# Servo-Power.net
KiCad netlist of a schematic drawn in Altium Designer
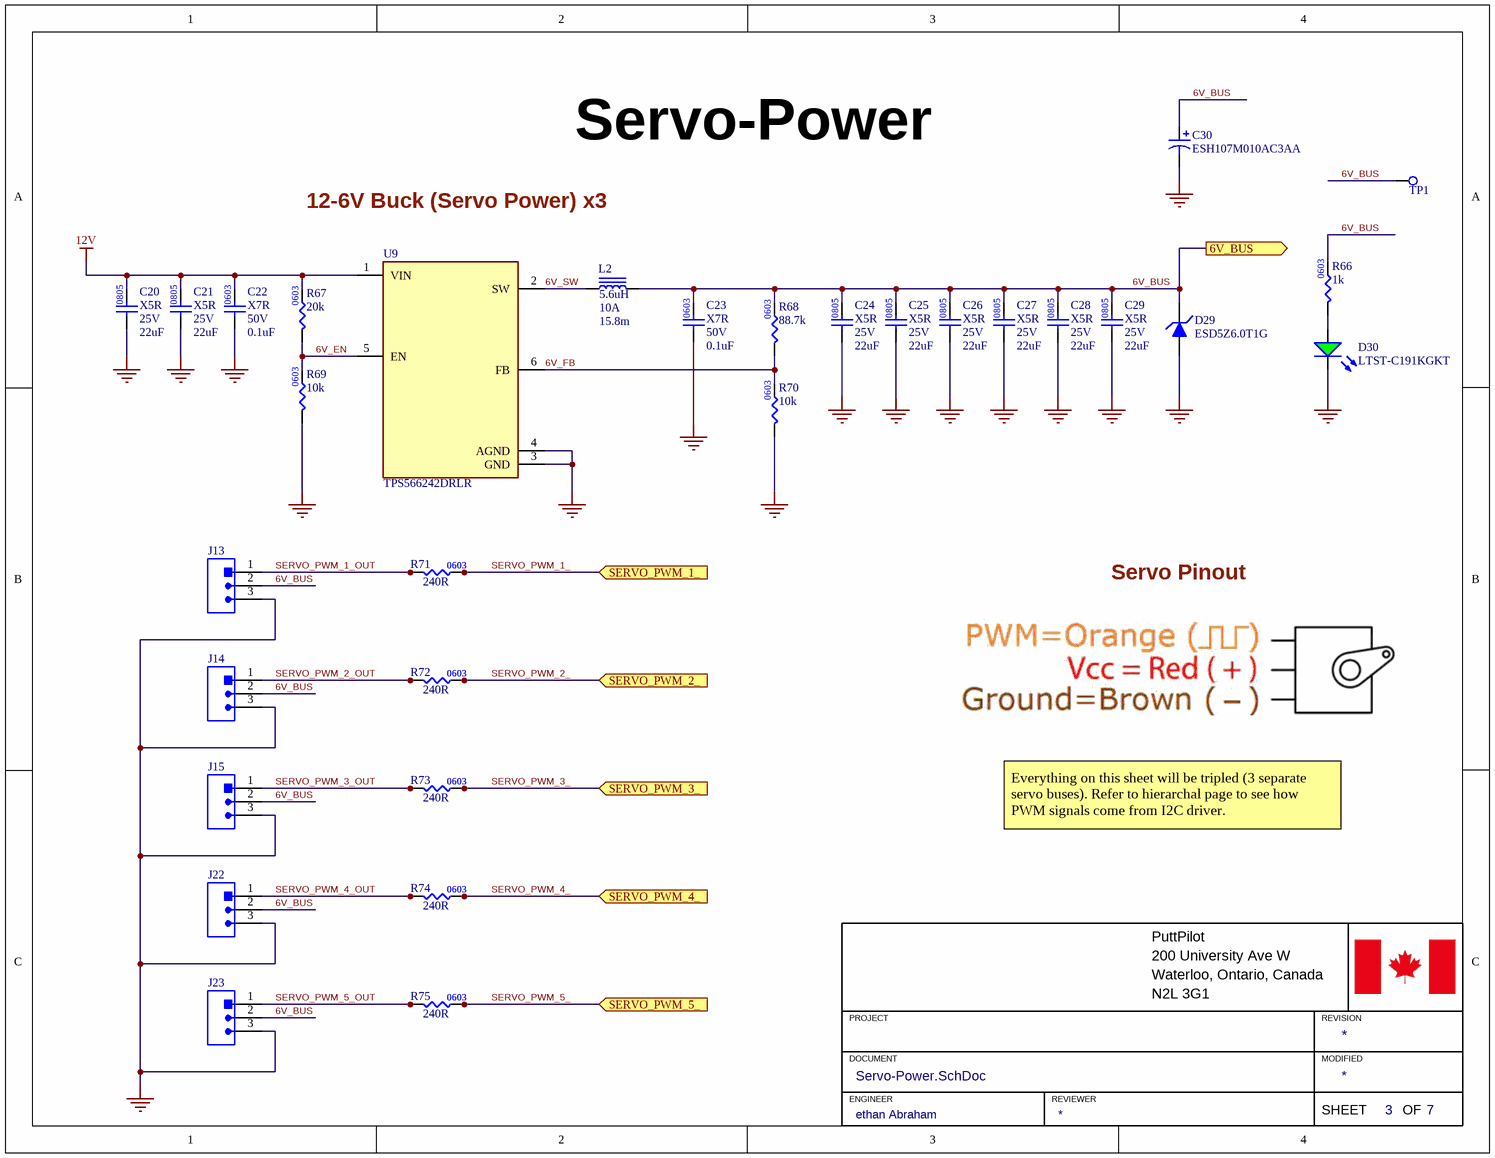
[diagram p0: Servo-Power.SchDoc]

(export (version "E")
  (design (tool "Eeschema 10.0.6"))
  (components
    (comp (ref "C20")
      (value "GRM21BR61E226ME44K")
      (footprint ".CAP_0805")
      (description "CAP CER 22uF 25V X5R 0805")
      (fields
        (field (name "MANUFACTURER") "Murata")
        (field (name "TEMPERATURE CHARACTERISTICS CODE") "X5R")
        (field (name "RATED DC VOLTAGE (URDC)") "25V")
        (field (name "CAPACITANCE") "22uF")
      )
      (libsource (lib "PuttPilot") (part "GRM21BR61E226ME44K"))
    )
    (comp (ref "C21")
      (value "GRM21BR61E226ME44K")
      (footprint ".CAP_0805")
      (description "CAP CER 22uF 25V X5R 0805")
      (fields
        (field (name "MANUFACTURER") "Murata")
        (field (name "TEMPERATURE CHARACTERISTICS CODE") "X5R")
        (field (name "RATED DC VOLTAGE (URDC)") "25V")
        (field (name "CAPACITANCE") "22uF")
      )
      (libsource (lib "PuttPilot") (part "GRM21BR61E226ME44K"))
    )
    (comp (ref "C22")
      (value "GCJ188R71H104KA12D")
      (footprint ".CAP_0603")
      (description "CAP CER 0.1uF 50V X7R 0603")
      (fields
        (field (name "MANUFACTURER") "Murata")
        (field (name "TEMPERATURE CHARACTERISTICS CODE") "X7R")
        (field (name "RATED DC VOLTAGE (URDC)") "50V")
        (field (name "CAPACITANCE") "0.1uF")
      )
      (libsource (lib "PuttPilot") (part "GCJ188R71H104KA12D"))
    )
    (comp (ref "C23")
      (value "GCJ188R71H104KA12D")
      (footprint ".CAP_0603")
      (description "CAP CER 0.1uF 50V X7R 0603")
      (fields
        (field (name "MANUFACTURER") "Murata")
        (field (name "TEMPERATURE CHARACTERISTICS CODE") "X7R")
        (field (name "RATED DC VOLTAGE (URDC)") "50V")
        (field (name "CAPACITANCE") "0.1uF")
      )
      (libsource (lib "PuttPilot") (part "GCJ188R71H104KA12D"))
    )
    (comp (ref "C24")
      (value "GRM21BR61E226ME44K")
      (footprint ".CAP_0805")
      (description "CAP CER 22uF 25V X5R 0805")
      (fields
        (field (name "MANUFACTURER") "Murata")
        (field (name "TEMPERATURE CHARACTERISTICS CODE") "X5R")
        (field (name "RATED DC VOLTAGE (URDC)") "25V")
        (field (name "CAPACITANCE") "22uF")
      )
      (libsource (lib "PuttPilot") (part "GRM21BR61E226ME44K"))
    )
    (comp (ref "C25")
      (value "GRM21BR61E226ME44K")
      (footprint ".CAP_0805")
      (description "CAP CER 22uF 25V X5R 0805")
      (fields
        (field (name "MANUFACTURER") "Murata")
        (field (name "TEMPERATURE CHARACTERISTICS CODE") "X5R")
        (field (name "RATED DC VOLTAGE (URDC)") "25V")
        (field (name "CAPACITANCE") "22uF")
      )
      (libsource (lib "PuttPilot") (part "GRM21BR61E226ME44K"))
    )
    (comp (ref "C26")
      (value "GRM21BR61E226ME44K")
      (footprint ".CAP_0805")
      (description "CAP CER 22uF 25V X5R 0805")
      (fields
        (field (name "MANUFACTURER") "Murata")
        (field (name "TEMPERATURE CHARACTERISTICS CODE") "X5R")
        (field (name "RATED DC VOLTAGE (URDC)") "25V")
        (field (name "CAPACITANCE") "22uF")
      )
      (libsource (lib "PuttPilot") (part "GRM21BR61E226ME44K"))
    )
    (comp (ref "C27")
      (value "GRM21BR61E226ME44K")
      (footprint ".CAP_0805")
      (description "CAP CER 22uF 25V X5R 0805")
      (fields
        (field (name "MANUFACTURER") "Murata")
        (field (name "TEMPERATURE CHARACTERISTICS CODE") "X5R")
        (field (name "RATED DC VOLTAGE (URDC)") "25V")
        (field (name "CAPACITANCE") "22uF")
      )
      (libsource (lib "PuttPilot") (part "GRM21BR61E226ME44K"))
    )
    (comp (ref "C28")
      (value "GRM21BR61E226ME44K")
      (footprint ".CAP_0805")
      (description "CAP CER 22uF 25V X5R 0805")
      (fields
        (field (name "MANUFACTURER") "Murata")
        (field (name "TEMPERATURE CHARACTERISTICS CODE") "X5R")
        (field (name "RATED DC VOLTAGE (URDC)") "25V")
        (field (name "CAPACITANCE") "22uF")
      )
      (libsource (lib "PuttPilot") (part "GRM21BR61E226ME44K"))
    )
    (comp (ref "C29")
      (value "GRM21BR61E226ME44K")
      (footprint ".CAP_0805")
      (description "CAP CER 22uF 25V X5R 0805")
      (fields
        (field (name "MANUFACTURER") "Murata")
        (field (name "TEMPERATURE CHARACTERISTICS CODE") "X5R")
        (field (name "RATED DC VOLTAGE (URDC)") "25V")
        (field (name "CAPACITANCE") "22uF")
      )
      (libsource (lib "PuttPilot") (part "GRM21BR61E226ME44K"))
    )
    (comp (ref "C30")
      (value "ESH107M010AC3AA")
      (footprint "ESH107M010AC3AA")
      (description "CAP ALUM 100uF 10V RAD THT")
      (libsource (lib "PuttPilot") (part "ESH107M010AC3AA"))
    )
    (comp (ref "D29")
      (value "ESD5Z6.0T1G")
      (footprint "ESD5Z6.0T1G")
      (description "DIODE TVS 6VWM")
      (fields (field (name "MANUFACTURER") "ON Semiconductor"))
      (libsource (lib "PuttPilot") (part "ESD5Z6.0T1G"))
    )
    (comp (ref "D30")
      (value "LTST-C191KGKT")
      (footprint ".LED_0603")
      (description "LED GREEN 2V 0603")
      (fields (field (name "MANUFACTURER") "Vishay Lite-On"))
      (libsource (lib "PuttPilot") (part "LTST-C191KGKT"))
    )
    (comp (ref "J13")
      (value "PRPC040SAAN-RC")
      (footprint "HEADER_3POS_2.54MM")
      (description "CONN HEADER VERT 3POS 2.54MM")
      (fields (field (name "MANUFACTURER") "Sullins"))
      (libsource (lib "PuttPilot") (part "PRPC040SAAN-RC"))
    )
    (comp (ref "J14")
      (value "PRPC040SAAN-RC")
      (footprint "HEADER_3POS_2.54MM")
      (description "CONN HEADER VERT 3POS 2.54MM")
      (fields (field (name "MANUFACTURER") "Sullins"))
      (libsource (lib "PuttPilot") (part "PRPC040SAAN-RC"))
    )
    (comp (ref "J15")
      (value "PRPC040SAAN-RC")
      (footprint "HEADER_3POS_2.54MM")
      (description "CONN HEADER VERT 3POS 2.54MM")
      (fields (field (name "MANUFACTURER") "Sullins"))
      (libsource (lib "PuttPilot") (part "PRPC040SAAN-RC"))
    )
    (comp (ref "J22")
      (value "PRPC040SAAN-RC")
      (footprint "HEADER_3POS_2.54MM")
      (description "CONN HEADER VERT 3POS 2.54MM")
      (fields (field (name "MANUFACTURER") "Sullins"))
      (libsource (lib "PuttPilot") (part "PRPC040SAAN-RC"))
    )
    (comp (ref "J23")
      (value "PRPC040SAAN-RC")
      (footprint "HEADER_3POS_2.54MM")
      (description "CONN HEADER VERT 3POS 2.54MM")
      (fields (field (name "MANUFACTURER") "Sullins"))
      (libsource (lib "PuttPilot") (part "PRPC040SAAN-RC"))
    )
    (comp (ref "L2")
      (value "SRP6060FA-5R6M")
      (footprint "SRP6060FA-5R6M")
      (description "FIXED IND 5.6uH 10A 15.8mOhm")
      (fields
        (field (name "MANUFACTURER") "Bourns")
        (field (name "INDUCTANCE") "5.6uH")
        (field (name "CURRENT RATING") "10A")
        (field (name "DC RESISTANCE") "15.8m")
      )
      (libsource (lib "PuttPilot") (part "SRP6060FA-5R6M"))
    )
    (comp (ref "R66")
      (value "RC0603FR-071KL")
      (footprint ".RES_0603")
      (description "RES 1K OHM 0603")
      (fields
        (field (name "MANUFACTURER") "Yageo")
        (field (name "TOLERANCE") "1%")
        (field (name "RESISTANCE") "1k")
      )
      (libsource (lib "PuttPilot") (part "RC0603FR-071KL"))
    )
    (comp (ref "R67")
      (value "ERJ-3EKF2002V")
      (footprint ".RES_0603")
      (description "RES 20K OHM 0603")
      (fields
        (field (name "MANUFACTURER") "Panasonic")
        (field (name "TOLERANCE") "1%")
        (field (name "RESISTANCE") "20k")
      )
      (libsource (lib "PuttPilot") (part "ERJ-3EKF2002V"))
    )
    (comp (ref "R68")
      (value "RC0603FR-0788K7L")
      (footprint ".RES_0603")
      (description "RES 88.7K OHM 0603")
      (fields
        (field (name "MANUFACTURER") "Yageo")
        (field (name "TOLERANCE") "1%")
        (field (name "RESISTANCE") "88.7k")
      )
      (libsource (lib "PuttPilot") (part "RC0603FR-0788K7L"))
    )
    (comp (ref "R69")
      (value "RC0603FR-0710KL")
      (footprint ".RES_0603")
      (description "RES 10K OHM 0603")
      (fields
        (field (name "MANUFACTURER") "Yageo")
        (field (name "TOLERANCE") "1%")
        (field (name "RESISTANCE") "10k")
      )
      (libsource (lib "PuttPilot") (part "RC0603FR-0710KL"))
    )
    (comp (ref "R70")
      (value "RC0603FR-0710KL")
      (footprint ".RES_0603")
      (description "RES 10K OHM 0603")
      (fields
        (field (name "MANUFACTURER") "Yageo")
        (field (name "TOLERANCE") "1%")
        (field (name "RESISTANCE") "10k")
      )
      (libsource (lib "PuttPilot") (part "RC0603FR-0710KL"))
    )
    (comp (ref "R71")
      (value "RC0603FR-07240RL")
      (footprint ".RES_0603")
      (description "RES 240 OHM 0603")
      (fields
        (field (name "MANUFACTURER") "Yageo")
        (field (name "TOLERANCE") "1%")
        (field (name "RESISTANCE") "240R")
      )
      (libsource (lib "PuttPilot") (part "RC0603FR-07240RL"))
    )
    (comp (ref "R72")
      (value "RC0603FR-07240RL")
      (footprint ".RES_0603")
      (description "RES 240 OHM 0603")
      (fields
        (field (name "MANUFACTURER") "Yageo")
        (field (name "TOLERANCE") "1%")
        (field (name "RESISTANCE") "240R")
      )
      (libsource (lib "PuttPilot") (part "RC0603FR-07240RL"))
    )
    (comp (ref "R73")
      (value "RC0603FR-07240RL")
      (footprint ".RES_0603")
      (description "RES 240 OHM 0603")
      (fields
        (field (name "MANUFACTURER") "Yageo")
        (field (name "TOLERANCE") "1%")
        (field (name "RESISTANCE") "240R")
      )
      (libsource (lib "PuttPilot") (part "RC0603FR-07240RL"))
    )
    (comp (ref "R74")
      (value "RC0603FR-07240RL")
      (footprint ".RES_0603")
      (description "RES 240 OHM 0603")
      (fields
        (field (name "MANUFACTURER") "Yageo")
        (field (name "TOLERANCE") "1%")
        (field (name "RESISTANCE") "240R")
      )
      (libsource (lib "PuttPilot") (part "RC0603FR-07240RL"))
    )
    (comp (ref "R75")
      (value "RC0603FR-07240RL")
      (footprint ".RES_0603")
      (description "RES 240 OHM 0603")
      (fields
        (field (name "MANUFACTURER") "Yageo")
        (field (name "TOLERANCE") "1%")
        (field (name "RESISTANCE") "240R")
      )
      (libsource (lib "PuttPilot") (part "RC0603FR-07240RL"))
    )
    (comp (ref "TP1")
      (value "RCWCTE")
      (footprint "RCWCTE")
      (description "SMT Test Point")
      (fields (field (name "MANUFACTURER") "KOA Speer"))
      (libsource (lib "PuttPilot") (part "RCWCTE"))
    )
    (comp (ref "U9")
      (value "TPS566242DRLR")
      (footprint "TPS566242DRLR")
      (description "BUCK 3V-16V 6A SOT-563")
      (fields (field (name "MANUFACTURER") "Texas Instruments"))
      (libsource (lib "PuttPilot") (part "TPS566242DRLR"))
    )
  )
  (nets
    (net (code "1") (name "/6V_BUS") (class "Default")
      (node (ref "C23") (pin "2") (pinfunction "2_2") (pintype "passive"))
      (node (ref "C24") (pin "2") (pinfunction "2_2") (pintype "passive"))
      (node (ref "C25") (pin "2") (pinfunction "2_2") (pintype "passive"))
      (node (ref "C26") (pin "2") (pinfunction "2_2") (pintype "passive"))
      (node (ref "C27") (pin "2") (pinfunction "2_2") (pintype "passive"))
      (node (ref "C28") (pin "2") (pinfunction "2_2") (pintype "passive"))
      (node (ref "C29") (pin "2") (pinfunction "2_2") (pintype "passive"))
      (node (ref "C30") (pin "1") (pinfunction "1_1") (pintype "passive"))
      (node (ref "D29") (pin "1") (pinfunction "Cathode_1") (pintype "passive"))
      (node (ref "J13") (pin "2") (pinfunction "2_2") (pintype "passive"))
      (node (ref "J14") (pin "2") (pinfunction "2_2") (pintype "passive"))
      (node (ref "J15") (pin "2") (pinfunction "2_2") (pintype "passive"))
      (node (ref "J22") (pin "2") (pinfunction "2_2") (pintype "passive"))
      (node (ref "J23") (pin "2") (pinfunction "2_2") (pintype "passive"))
      (node (ref "L2") (pin "2") (pinfunction "2_2") (pintype "passive"))
      (node (ref "R66") (pin "2") (pinfunction "2_2") (pintype "passive"))
      (node (ref "R68") (pin "2") (pinfunction "2_2") (pintype "passive"))
      (node (ref "TP1") (pin "1") (pinfunction "1_1") (pintype "passive"))
    )
    (net (code "2") (name "/6V_EN") (class "Default")
      (node (ref "R67") (pin "1") (pinfunction "1_1") (pintype "passive"))
      (node (ref "R69") (pin "2") (pinfunction "2_2") (pintype "passive"))
      (node (ref "U9") (pin "5") (pinfunction "EN_5") (pintype "passive"))
    )
    (net (code "3") (name "/6V_FB") (class "Default")
      (node (ref "R68") (pin "1") (pinfunction "1_1") (pintype "passive"))
      (node (ref "R70") (pin "2") (pinfunction "2_2") (pintype "passive"))
      (node (ref "U9") (pin "6") (pinfunction "FB_6") (pintype "passive"))
    )
    (net (code "4") (name "/6V_SW") (class "Default")
      (node (ref "L2") (pin "1") (pinfunction "1_1") (pintype "passive"))
      (node (ref "U9") (pin "2") (pinfunction "SW_2") (pintype "passive"))
    )
    (net (code "5") (name "/SERVO_PWM_1_") (class "Default")
      (node (ref "R71") (pin "2") (pinfunction "2_2") (pintype "passive"))
    )
    (net (code "6") (name "/SERVO_PWM_1_OUT") (class "Default")
      (node (ref "J13") (pin "1") (pinfunction "1_1") (pintype "passive"))
      (node (ref "R71") (pin "1") (pinfunction "1_1") (pintype "passive"))
    )
    (net (code "7") (name "/SERVO_PWM_2_") (class "Default")
      (node (ref "R72") (pin "2") (pinfunction "2_2") (pintype "passive"))
    )
    (net (code "8") (name "/SERVO_PWM_2_OUT") (class "Default")
      (node (ref "J14") (pin "1") (pinfunction "1_1") (pintype "passive"))
      (node (ref "R72") (pin "1") (pinfunction "1_1") (pintype "passive"))
    )
    (net (code "9") (name "/SERVO_PWM_3_") (class "Default")
      (node (ref "R73") (pin "2") (pinfunction "2_2") (pintype "passive"))
    )
    (net (code "10") (name "/SERVO_PWM_3_OUT") (class "Default")
      (node (ref "J15") (pin "1") (pinfunction "1_1") (pintype "passive"))
      (node (ref "R73") (pin "1") (pinfunction "1_1") (pintype "passive"))
    )
    (net (code "11") (name "/SERVO_PWM_4_") (class "Default")
      (node (ref "R74") (pin "2") (pinfunction "2_2") (pintype "passive"))
    )
    (net (code "12") (name "/SERVO_PWM_4_OUT") (class "Default")
      (node (ref "J22") (pin "1") (pinfunction "1_1") (pintype "passive"))
      (node (ref "R74") (pin "1") (pinfunction "1_1") (pintype "passive"))
    )
    (net (code "13") (name "/SERVO_PWM_5_") (class "Default")
      (node (ref "R75") (pin "2") (pinfunction "2_2") (pintype "passive"))
    )
    (net (code "14") (name "/SERVO_PWM_5_OUT") (class "Default")
      (node (ref "J23") (pin "1") (pinfunction "1_1") (pintype "passive"))
      (node (ref "R75") (pin "1") (pinfunction "1_1") (pintype "passive"))
    )
    (net (code "15") (name "12V") (class "Default")
      (node (ref "C20") (pin "2") (pinfunction "2_2") (pintype "passive"))
      (node (ref "C21") (pin "2") (pinfunction "2_2") (pintype "passive"))
      (node (ref "C22") (pin "2") (pinfunction "2_2") (pintype "passive"))
      (node (ref "R67") (pin "2") (pinfunction "2_2") (pintype "passive"))
      (node (ref "U9") (pin "1") (pinfunction "VIN_1") (pintype "passive"))
    )
    (net (code "16") (name "GND") (class "Default")
      (node (ref "C20") (pin "1") (pinfunction "1_1") (pintype "passive"))
      (node (ref "C21") (pin "1") (pinfunction "1_1") (pintype "passive"))
      (node (ref "C22") (pin "1") (pinfunction "1_1") (pintype "passive"))
      (node (ref "C23") (pin "1") (pinfunction "1_1") (pintype "passive"))
      (node (ref "C24") (pin "1") (pinfunction "1_1") (pintype "passive"))
      (node (ref "C25") (pin "1") (pinfunction "1_1") (pintype "passive"))
      (node (ref "C26") (pin "1") (pinfunction "1_1") (pintype "passive"))
      (node (ref "C27") (pin "1") (pinfunction "1_1") (pintype "passive"))
      (node (ref "C28") (pin "1") (pinfunction "1_1") (pintype "passive"))
      (node (ref "C29") (pin "1") (pinfunction "1_1") (pintype "passive"))
      (node (ref "C30") (pin "2") (pinfunction "2_2") (pintype "passive"))
      (node (ref "D29") (pin "2") (pinfunction "Anode_2") (pintype "passive"))
      (node (ref "D30") (pin "2") (pinfunction "K_2") (pintype "passive"))
      (node (ref "J13") (pin "3") (pinfunction "3_3") (pintype "passive"))
      (node (ref "J14") (pin "3") (pinfunction "3_3") (pintype "passive"))
      (node (ref "J15") (pin "3") (pinfunction "3_3") (pintype "passive"))
      (node (ref "J22") (pin "3") (pinfunction "3_3") (pintype "passive"))
      (node (ref "J23") (pin "3") (pinfunction "3_3") (pintype "passive"))
      (node (ref "R69") (pin "1") (pinfunction "1_1") (pintype "passive"))
      (node (ref "R70") (pin "1") (pinfunction "1_1") (pintype "passive"))
      (node (ref "U9") (pin "3") (pinfunction "GND_3") (pintype "passive"))
      (node (ref "U9") (pin "4") (pinfunction "AGND_4") (pintype "passive"))
    )
    (net (code "17") (name "Net-(D30-A)") (class "Default")
      (node (ref "D30") (pin "1") (pinfunction "A_1") (pintype "passive"))
      (node (ref "R66") (pin "1") (pinfunction "1_1") (pintype "passive"))
    )
  )
)
